# 02_BGT60LTR11AIP_Shield.net
KiCad netlist of a schematic drawn in Altium Designer
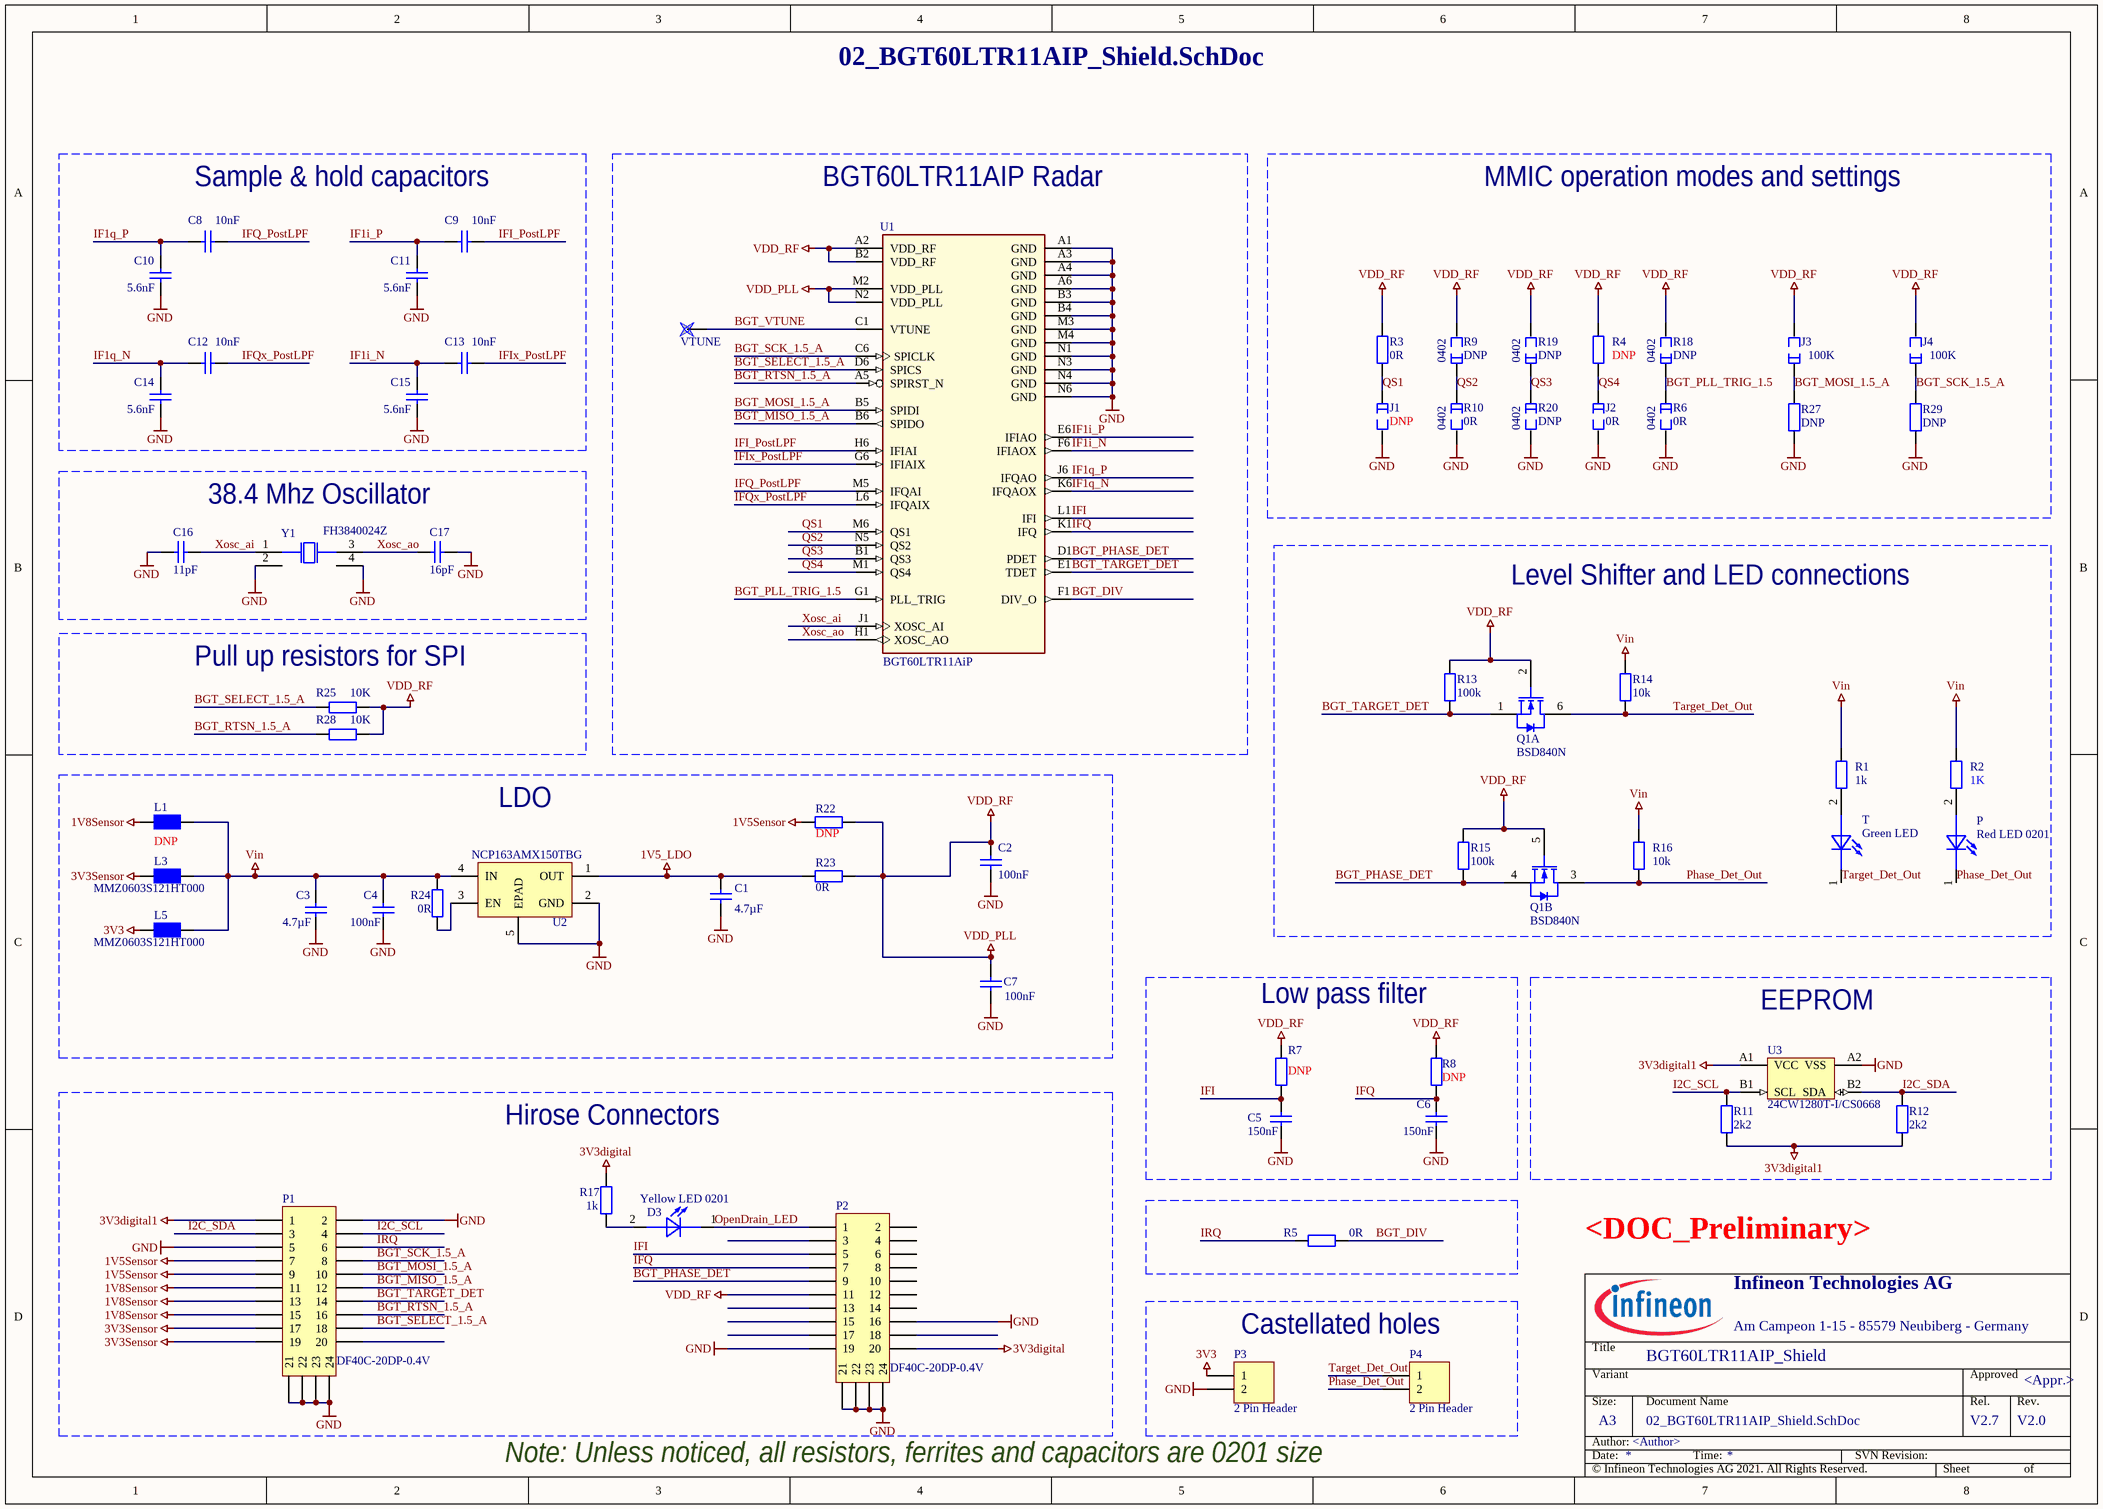
[diagram p0: 02_BGT60LTR11AIP_Shield.SchDoc]

(export (version "E")
  (design (tool "Eeschema 10.0.6"))
  (components
    (comp (ref "C1")
      (value "4.7µF")
      (footprint "C_0201")
      (description "Capacitor")
      (fields (field (name "PUBLISHER") "Altium Limited"))
      (libsource (lib "Miscellaneous Devices") (part "Cap"))
    )
    (comp (ref "C2")
      (value "100nF")
      (footprint "C_0201")
      (description "Capacitor")
      (fields (field (name "PUBLISHER") "Altium Limited"))
      (libsource (lib "Miscellaneous Devices") (part "Cap"))
    )
    (comp (ref "C3")
      (value "4.7µF")
      (footprint "C_0201")
      (description "Capacitor")
      (fields (field (name "PUBLISHER") "Altium Limited"))
      (libsource (lib "Miscellaneous Devices") (part "Cap"))
    )
    (comp (ref "C4")
      (value "100nF")
      (footprint "C_0201")
      (description "Capacitor")
      (fields (field (name "PUBLISHER") "Altium Limited"))
      (libsource (lib "Miscellaneous Devices") (part "Cap"))
    )
    (comp (ref "C5") (value "150nF") (footprint "C_0201") (libsource (lib "proj_lib") (part "Cap")))
    (comp (ref "C6") (value "150nF") (footprint "C_0201") (libsource (lib "proj_lib") (part "Cap")))
    (comp (ref "C7")
      (value "100nF")
      (footprint "C_0201")
      (description "Capacitor")
      (fields (field (name "PUBLISHER") "Altium Limited"))
      (libsource (lib "Miscellaneous Devices") (part "Cap"))
    )
    (comp (ref "C8") (value "10nF") (footprint "C_0201") (libsource (lib "proj_lib") (part "Cap")))
    (comp (ref "C9") (value "10nF") (footprint "C_0201") (libsource (lib "proj_lib") (part "Cap")))
    (comp (ref "C10") (value "5.6nF") (footprint "C_0201") (libsource (lib "proj_lib") (part "Cap")))
    (comp (ref "C11") (value "5.6nF") (footprint "C_0201") (libsource (lib "proj_lib") (part "Cap")))
    (comp (ref "C12") (value "10nF") (footprint "C_0201") (libsource (lib "proj_lib") (part "Cap")))
    (comp (ref "C13") (value "10nF") (footprint "C_0201") (libsource (lib "proj_lib") (part "Cap")))
    (comp (ref "C14") (value "5.6nF") (footprint "C_0201") (libsource (lib "proj_lib") (part "Cap")))
    (comp (ref "C15") (value "5.6nF") (footprint "C_0201") (libsource (lib "proj_lib") (part "Cap")))
    (comp (ref "C16")
      (value "11pF")
      (footprint "C_0201")
      (description "Capacitor")
      (fields (field (name "PUBLISHER") "Altium Limited"))
      (libsource (lib "Miscellaneous Devices") (part "Cap"))
    )
    (comp (ref "C17")
      (value "16pF")
      (footprint "C_0201")
      (description "Capacitor")
      (fields (field (name "PUBLISHER") "Altium Limited"))
      (libsource (lib "Miscellaneous Devices") (part "Cap"))
    )
    (comp (ref "D3")
      (value "Yellow LED 0201")
      (footprint "LED_0201")
      (description "XZMYR155W")
      (fields
        (field (name "LEGACY PARTNUMBER") "DIO00500016")
        (field (name "MANUFACTURER") "Rohm Semiconductors")
      )
      (libsource (lib "PCBLibraryData") (part "d_led_a"))
    )
    (comp (ref "J1")
      (value "DNP")
      (footprint "QS_Jumper")
      (description "3 pads for QS pins configuration (soldering needed)")
      (libsource (lib "BGT60LTR11_AIP") (part "QS_Jumper"))
    )
    (comp (ref "J2")
      (value "0R")
      (footprint "QS_Jumper")
      (description "3 pads for QS pins configuration (soldering needed)")
      (libsource (lib "BGT60LTR11_AIP") (part "QS_Jumper"))
    )
    (comp (ref "J3")
      (value "100K")
      (footprint "QS_Jumper")
      (description "3 pads for QS pins configuration (soldering needed)")
      (libsource (lib "BGT60LTR11_AIP") (part "QS_Jumper"))
    )
    (comp (ref "J4")
      (value "100K")
      (footprint "QS_Jumper")
      (description "3 pads for QS pins configuration (soldering needed)")
      (libsource (lib "BGT60LTR11_AIP") (part "QS_Jumper"))
    )
    (comp (ref "L1")
      (value "DNP")
      (footprint "R_0201")
      (description "SMD Ferrite Bead")
      (libsource (lib "Tjuefire") (part "INDUCTOR1"))
    )
    (comp (ref "L3")
      (value "MMZ0603S121HT000")
      (footprint "R_0201")
      (libsource (lib "Tjuefire") (part "INDUCTOR1"))
    )
    (comp (ref "L5")
      (value "MMZ0603S121HT000")
      (footprint "R_0201")
      (description "SMD Ferrite Bead")
      (libsource (lib "Tjuefire") (part "INDUCTOR1"))
    )
    (comp (ref "P")
      (value "Red LED 0201")
      (footprint "LED_0201")
      (description "XZMER155W")
      (fields (field (name "MANUFACTURER") "Rohm Semiconductors"))
      (libsource (lib "PCBLibraryData") (part "d_led_a"))
    )
    (comp (ref "P1")
      (value "DF40C-20DP-0.4V")
      (footprint "DF40C-20DP-0.4V")
      (description "Hirose DF40C-20DS-0.4V - 61GHz side")
      (libsource (lib "Hatvan") (part "DF40C-20DP-0.4V"))
    )
    (comp (ref "P2")
      (value "DF40C-20DP-0.4V")
      (footprint "DF40C-20DP-0.4V")
      (description "Hirose DF40C-20DS-0.4V - 61GHz side")
      (libsource (lib "Hatvan") (part "DF40C-20DP-0.4V"))
    )
    (comp (ref "P3")
      (value "2 Pin Header")
      (footprint "HDR1X2_Half")
      (description "Header, 2-Pin")
      (fields (field (name "PUBLISHER") "Altium Limited"))
      (libsource (lib "Miscellaneous Connectors") (part "Header 2"))
    )
    (comp (ref "P4")
      (value "2 Pin Header")
      (footprint "HDR1X2_Half")
      (description "Header, 2-Pin")
      (fields (field (name "PUBLISHER") "Altium Limited"))
      (libsource (lib "Miscellaneous Connectors") (part "Header 2"))
    )
    (comp (ref "Q1")
      (value "BSD840N")
      (footprint "INF-PG-SOT-363_N")
      (fields (field (name "MANUFACTURER") "Infineon"))
      (libsource (lib "BGT60LTR11_AIP") (part "BSD840N"))
    )
    (comp (ref "R1")
      (value "1k")
      (footprint "R_0201")
      (description "Resistor")
      (libsource (lib "Miscellaneous Devices") (part "Res2"))
    )
    (comp (ref "R2")
      (value "1K")
      (footprint "R_0201")
      (description "Resistor")
      (libsource (lib "Miscellaneous Devices") (part "Res2"))
    )
    (comp (ref "R3")
      (value "0R")
      (footprint "R_0201")
      (description "Resistor")
      (libsource (lib "Miscellaneous Devices") (part "Res2"))
    )
    (comp (ref "R4")
      (value "DNP")
      (footprint "R_0201")
      (description "Resistor")
      (libsource (lib "Miscellaneous Devices") (part "Res2"))
    )
    (comp (ref "R5")
      (value "0R")
      (footprint "R_0201")
      (description "Resistor")
      (libsource (lib "") (part "Res2_2"))
    )
    (comp (ref "R6")
      (value "0R")
      (footprint "RES_FastSolder_0402")
      (description "Resistor")
      (fields (field (name "ALTIUM_VALUE") "0402"))
      (libsource (lib "RES_FastSolder") (part "RES_FS"))
    )
    (comp (ref "R7")
      (value "DNP")
      (footprint "R_0201")
      (description "Resistor")
      (libsource (lib "Miscellaneous Devices") (part "Res2"))
    )
    (comp (ref "R8")
      (value "DNP")
      (footprint "R_0201")
      (description "Resistor")
      (libsource (lib "") (part "Res2_1"))
    )
    (comp (ref "R9")
      (value "DNP")
      (footprint "RES_FastSolder_0402")
      (description "Resistor")
      (fields (field (name "ALTIUM_VALUE") "0402"))
      (libsource (lib "RES_FastSolder") (part "RES_FS"))
    )
    (comp (ref "R10")
      (value "0R")
      (footprint "RES_FastSolder_0402")
      (description "Resistor")
      (fields (field (name "ALTIUM_VALUE") "0402"))
      (libsource (lib "RES_FastSolder") (part "RES_FS"))
    )
    (comp (ref "R11")
      (value "2k2")
      (footprint "R_0201")
      (description "Resistor")
      (libsource (lib "Miscellaneous Devices") (part "Res2"))
    )
    (comp (ref "R12")
      (value "2k2")
      (footprint "R_0201")
      (description "Resistor")
      (libsource (lib "Miscellaneous Devices") (part "Res2"))
    )
    (comp (ref "R13")
      (value "100k")
      (footprint "R_0201")
      (description "Resistor")
      (libsource (lib "Miscellaneous Devices") (part "Res2"))
    )
    (comp (ref "R14")
      (value "10k")
      (footprint "R_0201")
      (description "Resistor")
      (libsource (lib "Miscellaneous Devices") (part "Res2"))
    )
    (comp (ref "R15")
      (value "100k")
      (footprint "R_0201")
      (description "Resistor")
      (libsource (lib "Miscellaneous Devices") (part "Res2"))
    )
    (comp (ref "R16")
      (value "10k")
      (footprint "R_0201")
      (description "Resistor")
      (libsource (lib "Miscellaneous Devices") (part "Res2"))
    )
    (comp (ref "R17")
      (value "1k")
      (footprint "R_0201")
      (description "Resistor")
      (libsource (lib "Miscellaneous Devices") (part "Res2"))
    )
    (comp (ref "R18")
      (value "DNP")
      (footprint "RES_FastSolder_0402")
      (description "Resistor")
      (fields (field (name "ALTIUM_VALUE") "0402"))
      (libsource (lib "RES_FastSolder") (part "RES_FS"))
    )
    (comp (ref "R19")
      (value "DNP")
      (footprint "RES_FastSolder_0402")
      (description "Resistor")
      (fields (field (name "ALTIUM_VALUE") "0402"))
      (libsource (lib "RES_FastSolder") (part "RES_FS"))
    )
    (comp (ref "R20")
      (value "DNP")
      (footprint "RES_FastSolder_0402")
      (description "Resistor")
      (fields (field (name "ALTIUM_VALUE") "0402"))
      (libsource (lib "RES_FastSolder") (part "RES_FS"))
    )
    (comp (ref "R22")
      (value "DNP")
      (footprint "R_0201")
      (description "Resistor")
      (libsource (lib "") (part "Res2_2"))
    )
    (comp (ref "R23")
      (value "0R")
      (footprint "R_0201")
      (description "Resistor")
      (libsource (lib "") (part "Res2_2"))
    )
    (comp (ref "R24")
      (value "0R")
      (footprint "R_0201")
      (description "Resistor")
      (libsource (lib "Miscellaneous Devices") (part "Res2"))
    )
    (comp (ref "R25")
      (value "10K")
      (footprint "R_0201")
      (description "Resistor")
      (libsource (lib "") (part "Res2_2"))
    )
    (comp (ref "R27")
      (value "DNP")
      (footprint "R_0201")
      (description "Resistor")
      (libsource (lib "Miscellaneous Devices") (part "Res2"))
    )
    (comp (ref "R28")
      (value "10K")
      (footprint "R_0201")
      (description "Resistor")
      (libsource (lib "") (part "Res2_2"))
    )
    (comp (ref "R29")
      (value "DNP")
      (footprint "R_0201")
      (description "Resistor")
      (libsource (lib "Miscellaneous Devices") (part "Res2"))
    )
    (comp (ref "T")
      (value "Green LED")
      (footprint "LED_0201")
      (description "XZBGR155W5MAV")
      (fields (field (name "MANUFACTURER") "Rohm Semiconductors"))
      (libsource (lib "PCBLibraryData") (part "d_led_a"))
    )
    (comp (ref "U1")
      (value "BGT60LTR11AiP")
      (footprint "BGA42N50P13X7_670X330X56_new")
      (description "BGT60LTR11AiP, BGA 42 pins")
      (fields (field (name "MANUFACTURER") "Infineon Technologies"))
      (libsource (lib "PCBLibraryData") (part "BGT60LTR11_AIP"))
    )
    (comp (ref "U2")
      (value "NCP163AMX150TBG")
      (footprint "NCP177")
      (description "NCP163 - LDO 250mA, XDFN4,\r\nultra-low noise, high PSRR")
      (libsource (lib "Hatvan") (part "NCP177"))
    )
    (comp (ref "U3")
      (value "24CW1280T-I/CS0668")
      (footprint "WLCSP4 (CS0)")
      (description "128K I2C Serial EEPROM with Software Write Protection in CSP4 Package, 0.4mm Pin Pitch")
      (libsource (lib "IFXMemory") (part "24CW128X"))
    )
    (comp (ref "VTUNE")
      (value "Testpoint")
      (footprint "TP0.3MM")
      (libsource (lib "Hatvan") (part "P_PRUEFPAD"))
    )
    (comp (ref "Y1")
      (value "FH3840024Z")
      (footprint "NDK NX2520SA_NoBoarder")
      (fields (field (name "MANUFACTURER") "Nihon Dempa Kogyo"))
      (libsource (lib "PCBLibraryData") (part "y_std_4p-1"))
    )
  )
  (nets
    (net (code "1") (name "/BGT_DIV") (class "Default")
      (node (ref "R5") (pin "1") (pinfunction "1_1") (pintype "passive"))
      (node (ref "U1") (pin "F1") (pinfunction "DIV_O_F1") (pintype "output"))
    )
    (net (code "2") (name "/BGT_MISO_1.5_A") (class "Default")
      (node (ref "P1") (pin "12") (pinfunction "12_12") (pintype "passive"))
      (node (ref "U1") (pin "B6") (pinfunction "SPIDO_B6") (pintype "output"))
    )
    (net (code "3") (name "/BGT_MOSI_1.5_A") (class "Default")
      (node (ref "J3") (pin "2") (pinfunction "2_2") (pintype "passive"))
      (node (ref "P1") (pin "10") (pinfunction "10_10") (pintype "passive"))
      (node (ref "R27") (pin "2") (pinfunction "2_2") (pintype "passive"))
      (node (ref "U1") (pin "B5") (pinfunction "SPIDI_B5") (pintype "input"))
    )
    (net (code "4") (name "/BGT_PHASE_DET") (class "Default")
      (node (ref "P2") (pin "9") (pinfunction "9_9") (pintype "passive"))
      (node (ref "Q1") (pin "4") (pinfunction "SOURCE_4") (pintype "passive"))
      (node (ref "R15") (pin "1") (pinfunction "1_1") (pintype "passive"))
      (node (ref "U1") (pin "D1") (pinfunction "PDET_D1") (pintype "output"))
    )
    (net (code "5") (name "/BGT_PLL_TRIG_1.5") (class "Default")
      (node (ref "R18") (pin "2") (pinfunction "2_2") (pintype "passive"))
      (node (ref "R6") (pin "2") (pinfunction "2_2") (pintype "passive"))
      (node (ref "U1") (pin "G1") (pinfunction "PLL_TRIG_G1") (pintype "input"))
    )
    (net (code "6") (name "/BGT_RTSN_1.5_A") (class "Default")
      (node (ref "P1") (pin "16") (pinfunction "16_16") (pintype "passive"))
      (node (ref "R28") (pin "2") (pinfunction "2_2") (pintype "passive"))
      (node (ref "U1") (pin "A5") (pinfunction "SPIRST_N_A5") (pintype "input"))
    )
    (net (code "7") (name "/BGT_SCK_1.5_A") (class "Default")
      (node (ref "J4") (pin "2") (pinfunction "2_2") (pintype "passive"))
      (node (ref "P1") (pin "8") (pinfunction "8_8") (pintype "passive"))
      (node (ref "R29") (pin "2") (pinfunction "2_2") (pintype "passive"))
      (node (ref "U1") (pin "C6") (pinfunction "SPICLK_C6") (pintype "input"))
    )
    (net (code "8") (name "/BGT_SELECT_1.5_A") (class "Default")
      (node (ref "P1") (pin "18") (pinfunction "18_18") (pintype "passive"))
      (node (ref "R25") (pin "2") (pinfunction "2_2") (pintype "passive"))
      (node (ref "U1") (pin "D6") (pinfunction "SPICS_D6") (pintype "input"))
    )
    (net (code "9") (name "/BGT_TARGET_DET") (class "Default")
      (node (ref "P1") (pin "14") (pinfunction "14_14") (pintype "passive"))
      (node (ref "Q1") (pin "1") (pinfunction "SOURCE_1") (pintype "passive"))
      (node (ref "R13") (pin "1") (pinfunction "1_1") (pintype "passive"))
      (node (ref "U1") (pin "E1") (pinfunction "TDET_E1") (pintype "output"))
    )
    (net (code "10") (name "/BGT_VTUNE") (class "Default")
      (node (ref "U1") (pin "C1") (pinfunction "VTUNE_C1") (pintype "power_in"))
      (node (ref "VTUNE") (pin "1") (pinfunction "1_1") (pintype "passive"))
    )
    (net (code "11") (name "/I2C_SCL") (class "Default")
      (node (ref "P1") (pin "4") (pinfunction "4_4") (pintype "passive"))
      (node (ref "R11") (pin "2") (pinfunction "2_2") (pintype "passive"))
      (node (ref "U3") (pin "B1") (pinfunction "SCL_B1") (pintype "input"))
    )
    (net (code "12") (name "/I2C_SDA") (class "Default")
      (node (ref "P1") (pin "3") (pinfunction "3_3") (pintype "passive"))
      (node (ref "R12") (pin "2") (pinfunction "2_2") (pintype "passive"))
      (node (ref "U3") (pin "B2") (pinfunction "SDA_B2") (pintype "bidirectional"))
    )
    (net (code "13") (name "/IF1i_N") (class "Default")
      (node (ref "C13") (pin "1") (pinfunction "1_1") (pintype "passive"))
      (node (ref "C15") (pin "2") (pinfunction "2_2") (pintype "passive"))
      (node (ref "U1") (pin "F6") (pinfunction "IFIAOX_F6") (pintype "output"))
    )
    (net (code "14") (name "/IF1i_P") (class "Default")
      (node (ref "C11") (pin "2") (pinfunction "2_2") (pintype "passive"))
      (node (ref "C9") (pin "1") (pinfunction "1_1") (pintype "passive"))
      (node (ref "U1") (pin "E6") (pinfunction "IFIAO_E6") (pintype "output"))
    )
    (net (code "15") (name "/IF1q_N") (class "Default")
      (node (ref "C12") (pin "1") (pinfunction "1_1") (pintype "passive"))
      (node (ref "C14") (pin "2") (pinfunction "2_2") (pintype "passive"))
      (node (ref "U1") (pin "K6") (pinfunction "IFQAOX_K6") (pintype "output"))
    )
    (net (code "16") (name "/IF1q_P") (class "Default")
      (node (ref "C10") (pin "2") (pinfunction "2_2") (pintype "passive"))
      (node (ref "C8") (pin "1") (pinfunction "1_1") (pintype "passive"))
      (node (ref "U1") (pin "J6") (pinfunction "IFQAO_J6") (pintype "output"))
    )
    (net (code "17") (name "/IFI") (class "Default")
      (node (ref "C5") (pin "1") (pinfunction "1_1") (pintype "passive"))
      (node (ref "P2") (pin "5") (pinfunction "5_5") (pintype "passive"))
      (node (ref "R7") (pin "1") (pinfunction "1_1") (pintype "passive"))
      (node (ref "U1") (pin "L1") (pinfunction "IFI_L1") (pintype "output"))
    )
    (net (code "18") (name "/IFI_PostLPF") (class "Default")
      (node (ref "C9") (pin "2") (pinfunction "2_2") (pintype "passive"))
      (node (ref "U1") (pin "H6") (pinfunction "IFIAI_H6") (pintype "input"))
    )
    (net (code "19") (name "/IFIx_PostLPF") (class "Default")
      (node (ref "C13") (pin "2") (pinfunction "2_2") (pintype "passive"))
      (node (ref "U1") (pin "G6") (pinfunction "IFIAIX_G6") (pintype "input"))
    )
    (net (code "20") (name "/IFQ") (class "Default")
      (node (ref "C6") (pin "2") (pinfunction "2_2") (pintype "passive"))
      (node (ref "P2") (pin "7") (pinfunction "7_7") (pintype "passive"))
      (node (ref "R8") (pin "2") (pinfunction "2_2") (pintype "passive"))
      (node (ref "U1") (pin "K1") (pinfunction "IFQ_K1") (pintype "output"))
    )
    (net (code "21") (name "/IFQ_PostLPF") (class "Default")
      (node (ref "C8") (pin "2") (pinfunction "2_2") (pintype "passive"))
      (node (ref "U1") (pin "M5") (pinfunction "IFQAI_M5") (pintype "input"))
    )
    (net (code "22") (name "/IFQx_PostLPF") (class "Default")
      (node (ref "C12") (pin "2") (pinfunction "2_2") (pintype "passive"))
      (node (ref "U1") (pin "L6") (pinfunction "IFQAIX_L6") (pintype "input"))
    )
    (net (code "23") (name "/IRQ") (class "Default")
      (node (ref "P1") (pin "6") (pinfunction "6_6") (pintype "passive"))
      (node (ref "R5") (pin "2") (pinfunction "2_2") (pintype "passive"))
    )
    (net (code "24") (name "/OpenDrain_LED") (class "Default")
      (node (ref "D3") (pin "1") (pinfunction "Cathode_1") (pintype "passive"))
      (node (ref "P2") (pin "1") (pinfunction "1_1") (pintype "passive"))
    )
    (net (code "25") (name "/Phase_Det_Out") (class "Default")
      (node (ref "P") (pin "1") (pinfunction "Cathode_1") (pintype "passive"))
      (node (ref "P4") (pin "2") (pinfunction "2_2") (pintype "passive"))
      (node (ref "Q1") (pin "3") (pinfunction "DRAIN_3") (pintype "passive"))
      (node (ref "R16") (pin "1") (pinfunction "1_1") (pintype "passive"))
    )
    (net (code "26") (name "/QS1") (class "Default")
      (node (ref "J1") (pin "2") (pinfunction "2_2") (pintype "passive"))
      (node (ref "R3") (pin "1") (pinfunction "1_1") (pintype "passive"))
      (node (ref "U1") (pin "M6") (pinfunction "QS1_M6") (pintype "input"))
    )
    (net (code "27") (name "/QS2") (class "Default")
      (node (ref "R10") (pin "2") (pinfunction "2_2") (pintype "passive"))
      (node (ref "R9") (pin "2") (pinfunction "2_2") (pintype "passive"))
      (node (ref "U1") (pin "N5") (pinfunction "QS2_N5") (pintype "input"))
    )
    (net (code "28") (name "/QS3") (class "Default")
      (node (ref "R19") (pin "2") (pinfunction "2_2") (pintype "passive"))
      (node (ref "R20") (pin "2") (pinfunction "2_2") (pintype "passive"))
      (node (ref "U1") (pin "B1") (pinfunction "QS3_B1") (pintype "input"))
    )
    (net (code "29") (name "/QS4") (class "Default")
      (node (ref "J2") (pin "2") (pinfunction "2_2") (pintype "passive"))
      (node (ref "R4") (pin "1") (pinfunction "1_1") (pintype "passive"))
      (node (ref "U1") (pin "M1") (pinfunction "QS4_M1") (pintype "input"))
    )
    (net (code "30") (name "/Target_Det_Out") (class "Default")
      (node (ref "P4") (pin "1") (pinfunction "1_1") (pintype "passive"))
      (node (ref "Q1") (pin "6") (pinfunction "DRAIN_6") (pintype "passive"))
      (node (ref "R14") (pin "1") (pinfunction "1_1") (pintype "passive"))
      (node (ref "T") (pin "1") (pinfunction "Cathode_1") (pintype "passive"))
    )
    (net (code "31") (name "/Xosc_ai") (class "Default")
      (node (ref "C16") (pin "1") (pinfunction "1_1") (pintype "passive"))
      (node (ref "U1") (pin "J1") (pinfunction "XOSC_AI_J1") (pintype "input"))
      (node (ref "Y1") (pin "1") (pinfunction "1_1") (pintype "passive"))
    )
    (net (code "32") (name "/Xosc_ao") (class "Default")
      (node (ref "C17") (pin "2") (pinfunction "2_2") (pintype "passive"))
      (node (ref "U1") (pin "H1") (pinfunction "XOSC_AO_H1") (pintype "output"))
      (node (ref "Y1") (pin "3") (pinfunction "3_3") (pintype "passive"))
    )
    (net (code "33") (name "1V5Sensor") (class "Default")
      (node (ref "P1") (pin "7") (pinfunction "7_7") (pintype "passive"))
      (node (ref "P1") (pin "9") (pinfunction "9_9") (pintype "passive"))
      (node (ref "R22") (pin "2") (pinfunction "2_2") (pintype "passive"))
    )
    (net (code "34") (name "1V5_LDO") (class "Default")
      (node (ref "C1") (pin "2") (pinfunction "2_2") (pintype "passive"))
      (node (ref "R23") (pin "2") (pinfunction "2_2") (pintype "passive"))
      (node (ref "U2") (pin "1") (pinfunction "OUT_1") (pintype "passive"))
    )
    (net (code "35") (name "1V8Sensor") (class "Default")
      (node (ref "L1") (pin "1") (pinfunction "1_1") (pintype "passive"))
      (node (ref "P1") (pin "11") (pinfunction "11_11") (pintype "passive"))
      (node (ref "P1") (pin "13") (pinfunction "13_13") (pintype "passive"))
      (node (ref "P1") (pin "15") (pinfunction "15_15") (pintype "passive"))
    )
    (net (code "36") (name "3V3") (class "Default")
      (node (ref "L5") (pin "1") (pinfunction "1_1") (pintype "passive"))
      (node (ref "P3") (pin "1") (pinfunction "1_1") (pintype "passive"))
    )
    (net (code "37") (name "3V3Sensor") (class "Default")
      (node (ref "L3") (pin "1") (pinfunction "1_1") (pintype "passive"))
      (node (ref "P1") (pin "17") (pinfunction "17_17") (pintype "passive"))
      (node (ref "P1") (pin "19") (pinfunction "19_19") (pintype "passive"))
    )
    (net (code "38") (name "3V3digital") (class "Default")
      (node (ref "P2") (pin "20") (pinfunction "20_20") (pintype "passive"))
      (node (ref "R17") (pin "2") (pinfunction "2_2") (pintype "passive"))
    )
    (net (code "39") (name "3V3digital1") (class "Default")
      (node (ref "P1") (pin "1") (pinfunction "1_1") (pintype "passive"))
      (node (ref "R11") (pin "1") (pinfunction "1_1") (pintype "passive"))
      (node (ref "R12") (pin "1") (pinfunction "1_1") (pintype "passive"))
      (node (ref "U3") (pin "A1") (pinfunction "VCC_A1") (pintype "passive"))
    )
    (net (code "40") (name "GND") (class "Default")
      (node (ref "C1") (pin "1") (pinfunction "1_1") (pintype "passive"))
      (node (ref "C10") (pin "1") (pinfunction "1_1") (pintype "passive"))
      (node (ref "C11") (pin "1") (pinfunction "1_1") (pintype "passive"))
      (node (ref "C14") (pin "1") (pinfunction "1_1") (pintype "passive"))
      (node (ref "C15") (pin "1") (pinfunction "1_1") (pintype "passive"))
      (node (ref "C16") (pin "2") (pinfunction "2_2") (pintype "passive"))
      (node (ref "C17") (pin "1") (pinfunction "1_1") (pintype "passive"))
      (node (ref "C2") (pin "1") (pinfunction "1_1") (pintype "passive"))
      (node (ref "C3") (pin "1") (pinfunction "1_1") (pintype "passive"))
      (node (ref "C4") (pin "1") (pinfunction "1_1") (pintype "passive"))
      (node (ref "C5") (pin "2") (pinfunction "2_2") (pintype "passive"))
      (node (ref "C6") (pin "1") (pinfunction "1_1") (pintype "passive"))
      (node (ref "C7") (pin "1") (pinfunction "1_1") (pintype "passive"))
      (node (ref "J1") (pin "1") (pinfunction "1_1") (pintype "passive"))
      (node (ref "J2") (pin "1") (pinfunction "1_1") (pintype "passive"))
      (node (ref "P1") (pin "2") (pinfunction "2_2") (pintype "passive"))
      (node (ref "P1") (pin "21") (pinfunction "21_21") (pintype "passive"))
      (node (ref "P1") (pin "22") (pinfunction "22_22") (pintype "passive"))
      (node (ref "P1") (pin "23") (pinfunction "23_23") (pintype "passive"))
      (node (ref "P1") (pin "24") (pinfunction "24_24") (pintype "passive"))
      (node (ref "P1") (pin "5") (pinfunction "5_5") (pintype "passive"))
      (node (ref "P2") (pin "16") (pinfunction "16_16") (pintype "passive"))
      (node (ref "P2") (pin "19") (pinfunction "19_19") (pintype "passive"))
      (node (ref "P2") (pin "21") (pinfunction "21_21") (pintype "passive"))
      (node (ref "P2") (pin "22") (pinfunction "22_22") (pintype "passive"))
      (node (ref "P2") (pin "23") (pinfunction "23_23") (pintype "passive"))
      (node (ref "P2") (pin "24") (pinfunction "24_24") (pintype "passive"))
      (node (ref "P3") (pin "2") (pinfunction "2_2") (pintype "passive"))
      (node (ref "R10") (pin "1") (pinfunction "1_1") (pintype "passive"))
      (node (ref "R20") (pin "1") (pinfunction "1_1") (pintype "passive"))
      (node (ref "R27") (pin "1") (pinfunction "1_1") (pintype "passive"))
      (node (ref "R29") (pin "1") (pinfunction "1_1") (pintype "passive"))
      (node (ref "R6") (pin "1") (pinfunction "1_1") (pintype "passive"))
      (node (ref "U1") (pin "A1") (pinfunction "GND_A1") (pintype "power_in"))
      (node (ref "U1") (pin "A3") (pinfunction "GND_A3") (pintype "power_in"))
      (node (ref "U1") (pin "A4") (pinfunction "GND_A4") (pintype "power_in"))
      (node (ref "U1") (pin "A6") (pinfunction "GND_A6") (pintype "power_in"))
      (node (ref "U1") (pin "B3") (pinfunction "GND_B3") (pintype "power_in"))
      (node (ref "U1") (pin "B4") (pinfunction "GND_B4") (pintype "power_in"))
      (node (ref "U1") (pin "M3") (pinfunction "GND_M3") (pintype "power_in"))
      (node (ref "U1") (pin "M4") (pinfunction "GND_M4") (pintype "power_in"))
      (node (ref "U1") (pin "N1") (pinfunction "GND_N1") (pintype "power_in"))
      (node (ref "U1") (pin "N3") (pinfunction "GND_N3") (pintype "power_in"))
      (node (ref "U1") (pin "N4") (pinfunction "GND_N4") (pintype "power_in"))
      (node (ref "U1") (pin "N6") (pinfunction "GND_N6") (pintype "power_in"))
      (node (ref "U2") (pin "2") (pinfunction "GND_2") (pintype "passive"))
      (node (ref "U2") (pin "5") (pinfunction "EPAD_5") (pintype "passive"))
      (node (ref "U3") (pin "A2") (pinfunction "VSS_A2") (pintype "passive"))
      (node (ref "Y1") (pin "2") (pinfunction "2_2") (pintype "power_in"))
      (node (ref "Y1") (pin "4") (pinfunction "4_4") (pintype "power_in"))
    )
    (net (code "41") (name "Net-(D3-Anode)") (class "Default")
      (node (ref "D3") (pin "2") (pinfunction "Anode_2") (pintype "passive"))
      (node (ref "R17") (pin "1") (pinfunction "1_1") (pintype "passive"))
    )
    (net (code "42") (name "Net-(P-Anode)") (class "Default")
      (node (ref "P") (pin "2") (pinfunction "Anode_2") (pintype "passive"))
      (node (ref "R2") (pin "1") (pinfunction "1_1") (pintype "passive"))
    )
    (net (code "43") (name "Net-(T-Anode)") (class "Default")
      (node (ref "R1") (pin "1") (pinfunction "1_1") (pintype "passive"))
      (node (ref "T") (pin "2") (pinfunction "Anode_2") (pintype "passive"))
    )
    (net (code "44") (name "Net-(U2-EN)") (class "Default")
      (node (ref "R24") (pin "1") (pinfunction "1_1") (pintype "passive"))
      (node (ref "U2") (pin "3") (pinfunction "EN_3") (pintype "passive"))
    )
    (net (code "45") (name "VDD_PLL") (class "Default")
      (node (ref "C2") (pin "2") (pinfunction "2_2") (pintype "passive"))
      (node (ref "C7") (pin "2") (pinfunction "2_2") (pintype "passive"))
      (node (ref "J3") (pin "1") (pinfunction "1_1") (pintype "passive"))
      (node (ref "J4") (pin "1") (pinfunction "1_1") (pintype "passive"))
      (node (ref "P2") (pin "11") (pinfunction "11_11") (pintype "passive"))
      (node (ref "Q1") (pin "2") (pinfunction "GATE_2") (pintype "passive"))
      (node (ref "Q1") (pin "5") (pinfunction "GATE_5") (pintype "passive"))
      (node (ref "R13") (pin "2") (pinfunction "2_2") (pintype "passive"))
      (node (ref "R15") (pin "2") (pinfunction "2_2") (pintype "passive"))
      (node (ref "R18") (pin "1") (pinfunction "1_1") (pintype "passive"))
      (node (ref "R19") (pin "1") (pinfunction "1_1") (pintype "passive"))
      (node (ref "R22") (pin "1") (pinfunction "1_1") (pintype "passive"))
      (node (ref "R23") (pin "1") (pinfunction "1_1") (pintype "passive"))
      (node (ref "R25") (pin "1") (pinfunction "1_1") (pintype "passive"))
      (node (ref "R28") (pin "1") (pinfunction "1_1") (pintype "passive"))
      (node (ref "R3") (pin "2") (pinfunction "2_2") (pintype "passive"))
      (node (ref "R4") (pin "2") (pinfunction "2_2") (pintype "passive"))
      (node (ref "R7") (pin "2") (pinfunction "2_2") (pintype "passive"))
      (node (ref "R8") (pin "1") (pinfunction "1_1") (pintype "passive"))
      (node (ref "R9") (pin "1") (pinfunction "1_1") (pintype "passive"))
      (node (ref "U1") (pin "A2") (pinfunction "VDD_RF_A2") (pintype "power_in"))
      (node (ref "U1") (pin "B2") (pinfunction "VDD_RF_B2") (pintype "power_in"))
      (node (ref "U1") (pin "M2") (pinfunction "VDD_PLL_M2") (pintype "power_in"))
      (node (ref "U1") (pin "N2") (pinfunction "VDD_PLL_N2") (pintype "power_in"))
    )
    (net (code "46") (name "Vin") (class "Default")
      (node (ref "C3") (pin "2") (pinfunction "2_2") (pintype "passive"))
      (node (ref "C4") (pin "2") (pinfunction "2_2") (pintype "passive"))
      (node (ref "L1") (pin "2") (pinfunction "2_2") (pintype "passive"))
      (node (ref "L3") (pin "2") (pinfunction "2_2") (pintype "passive"))
      (node (ref "L5") (pin "2") (pinfunction "2_2") (pintype "passive"))
      (node (ref "R1") (pin "2") (pinfunction "2_2") (pintype "passive"))
      (node (ref "R14") (pin "2") (pinfunction "2_2") (pintype "passive"))
      (node (ref "R16") (pin "2") (pinfunction "2_2") (pintype "passive"))
      (node (ref "R2") (pin "2") (pinfunction "2_2") (pintype "passive"))
      (node (ref "R24") (pin "2") (pinfunction "2_2") (pintype "passive"))
      (node (ref "U2") (pin "4") (pinfunction "IN_4") (pintype "passive"))
    )
    (net (code "47") (name "unconnected-(P1-Pad20)") (class "Default")
      (node (ref "P1") (pin "20") (pinfunction "20_20") (pintype "passive"))
    )
    (net (code "48") (name "unconnected-(P2-Pad2)") (class "Default")
      (node (ref "P2") (pin "2") (pinfunction "2_2") (pintype "passive"))
    )
    (net (code "49") (name "unconnected-(P2-Pad3)") (class "Default")
      (node (ref "P2") (pin "3") (pinfunction "3_3") (pintype "passive"))
    )
    (net (code "50") (name "unconnected-(P2-Pad4)") (class "Default")
      (node (ref "P2") (pin "4") (pinfunction "4_4") (pintype "passive"))
    )
    (net (code "51") (name "unconnected-(P2-Pad6)") (class "Default")
      (node (ref "P2") (pin "6") (pinfunction "6_6") (pintype "passive"))
    )
    (net (code "52") (name "unconnected-(P2-Pad8)") (class "Default")
      (node (ref "P2") (pin "8") (pinfunction "8_8") (pintype "passive"))
    )
    (net (code "53") (name "unconnected-(P2-Pad10)") (class "Default")
      (node (ref "P2") (pin "10") (pinfunction "10_10") (pintype "passive"))
    )
    (net (code "54") (name "unconnected-(P2-Pad12)") (class "Default")
      (node (ref "P2") (pin "12") (pinfunction "12_12") (pintype "passive"))
    )
    (net (code "55") (name "unconnected-(P2-Pad13)") (class "Default")
      (node (ref "P2") (pin "13") (pinfunction "13_13") (pintype "passive"))
    )
    (net (code "56") (name "unconnected-(P2-Pad14)") (class "Default")
      (node (ref "P2") (pin "14") (pinfunction "14_14") (pintype "passive"))
    )
    (net (code "57") (name "unconnected-(P2-Pad15)") (class "Default")
      (node (ref "P2") (pin "15") (pinfunction "15_15") (pintype "passive"))
    )
    (net (code "58") (name "unconnected-(P2-Pad17)") (class "Default")
      (node (ref "P2") (pin "17") (pinfunction "17_17") (pintype "passive"))
    )
    (net (code "59") (name "unconnected-(P2-Pad18)") (class "Default")
      (node (ref "P2") (pin "18") (pinfunction "18_18") (pintype "passive"))
    )
  )
)
